# Digital_Clock.net
KiCad netlist of a schematic drawn in Altium Designer
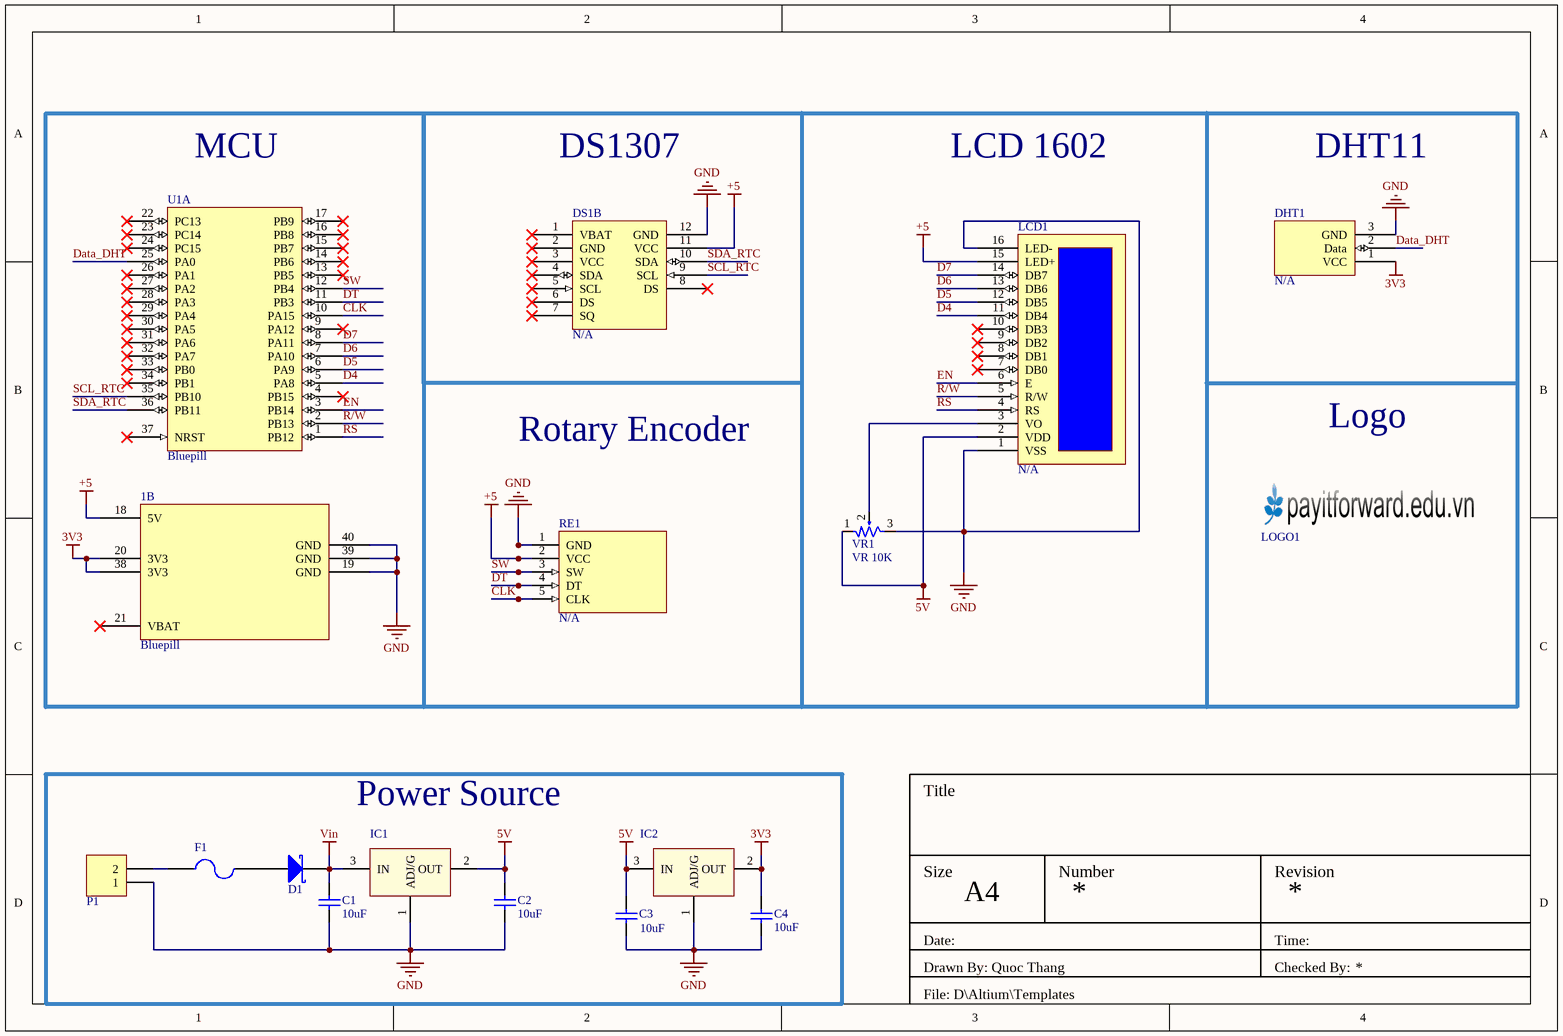
[diagram p0: Digital_Clock.SchDoc]

(export (version "E")
  (design (tool "Eeschema 10.0.6"))
  (components
    (comp (ref "1")
      (value "Bluepill")
      (footprint "STM32F103C8T6")
      (fields (field (name "MANUFACTURER") "STMicroelectronics"))
      (libsource (lib "Altium_library_module_kit") (part "STM32F103C8T6"))
    )
    (comp (ref "C1")
      (value "10uF")
      (footprint "CAP-SM-0805")
      (description "Capacitor")
      (fields (field (name "Comment") "Cap Non-Pol SMD"))
      (libsource (lib "PIF_Library") (part "Cap Non-Pol SMD"))
    )
    (comp (ref "C2")
      (value "10uF")
      (footprint "CAP-SM-0805")
      (description "Capacitor")
      (fields (field (name "Comment") "Cap Non-Pol SMD"))
      (libsource (lib "PIF_Library") (part "Cap Non-Pol SMD"))
    )
    (comp (ref "C3")
      (value "10uF")
      (footprint "CAP-SM-0805")
      (description "Capacitor")
      (fields (field (name "Comment") "Cap Non-Pol SMD"))
      (libsource (lib "PIF_Library") (part "Cap Non-Pol SMD"))
    )
    (comp (ref "C4")
      (value "10uF")
      (footprint "CAP-SM-0805")
      (description "Capacitor")
      (fields (field (name "Comment") "Cap Non-Pol SMD"))
      (libsource (lib "PIF_Library") (part "Cap Non-Pol SMD"))
    )
    (comp (ref "D1")
      (value "D Schottky")
      (footprint "SS34")
      (description "Schottky Diode")
      (fields (field (name "PUBLISHER") "Altium Limited"))
      (libsource (lib "PIF_Library") (part "D Schottky"))
    )
    (comp (ref "DHT1")
      (value "N/A")
      (footprint "DHT11")
      (description "Temperature Humidity Sensor 16bi")
      (fields (field (name "MANUFACTURER") "UNIVERSAL-SOLDER Electronics Ltd"))
      (libsource (lib "Altium_library_module_kit") (part "DHT11"))
    )
    (comp (ref "DS1")
      (value "N/A")
      (footprint "DS1307")
      (description "IC RTC CLOCK/CALENDAR I2C 8DIP")
      (fields (field (name "MANUFACTURER") "Analog Devices Inc./Maxim Integrated"))
      (libsource (lib "Altium_library_module_kit") (part "DS1307"))
    )
    (comp (ref "F1") (value "Fuse") (footprint "FUSE SMD") (libsource (lib "PIF_Library") (part "Fuse")))
    (comp (ref "IC1")
      (value "LM1117")
      (footprint "SOT223-4N")
      (description "Available in 1.8V, 2.5V, 2.85V, 3.3V, 5V, and  Adjustable Versions")
      (libsource (lib "PIF_Library") (part "LM1117"))
    )
    (comp (ref "IC2")
      (value "LM1117")
      (footprint "SOT223-4N")
      (description "Available in 1.8V, 2.5V, 2.85V, 3.3V, 5V, and  Adjustable Versions")
      (libsource (lib "PIF_Library") (part "LM1117"))
    )
    (comp (ref "LCD1")
      (value "N/A")
      (footprint "LCD1602")
      (description "BLUE LCD 1602 2x16 Character Mat")
      (fields (field (name "MANUFACTURER") "UNIVERSAL-SOLDER Electronics Ltd"))
      (libsource (lib "Altium_library_module_kit") (part "LCD1602"))
    )
    (comp (ref "LOGO1")
      (value "LOGO PIF")
      (footprint "PIF LOGO SMALL TOP")
      (libsource (lib "PIF_Library") (part "LOGO PIF"))
    )
    (comp (ref "P1")
      (value "Domino 2")
      (footprint "DOMINO 2- 5mm")
      (description "Domino, 2-Pin")
      (fields (field (name "PUBLISHER") "Altium Limited"))
      (libsource (lib "PIF_Library") (part "Domino 2"))
    )
    (comp (ref "RE1")
      (value "N/A")
      (footprint "Rotary_Encoder")
      (description "ROTARY ENCODER MECHANICAL 16PPR")
      (fields (field (name "MANUFACTURER") "CUI Devices"))
      (libsource (lib "Altium_library_module_kit") (part "Rotary Encoder"))
    )
    (comp (ref "U1")
      (value "Bluepill")
      (footprint "STM32F103C8T6")
      (fields (field (name "MANUFACTURER") "STMicroelectronics"))
      (libsource (lib "") (part "STM32F103C8T6_1"))
    )
    (comp (ref "VR1")
      (value "VR 10K")
      (footprint "Varistor 1")
      (description "Var Resistor")
      (fields (field (name "Comment") "10K"))
      (libsource (lib "PIF_Library") (part "Var Resistor"))
    )
  )
  (nets
    (net (code "1") (name "+5") (class "Default")
      (node (ref "1") (pin "18") (pinfunction "5V_18") (pintype "power_in"))
      (node (ref "DS1") (pin "11") (pinfunction "VCC_11") (pintype "power_in"))
      (node (ref "LCD1") (pin "15") (pinfunction "LED+_15") (pintype "power_in"))
      (node (ref "RE1") (pin "2") (pinfunction "VCC_2") (pintype "power_in"))
    )
    (net (code "2") (name "/CLK") (class "Default")
      (node (ref "RE1") (pin "5") (pinfunction "CLK_5") (pintype "input"))
      (node (ref "U1") (pin "10") (pinfunction "PA15_10") (pintype "bidirectional"))
    )
    (net (code "3") (name "/D4") (class "Default")
      (node (ref "LCD1") (pin "11") (pinfunction "DB4_11") (pintype "bidirectional"))
      (node (ref "U1") (pin "5") (pinfunction "PA8_5") (pintype "bidirectional"))
    )
    (net (code "4") (name "/D5") (class "Default")
      (node (ref "LCD1") (pin "12") (pinfunction "DB5_12") (pintype "bidirectional"))
      (node (ref "U1") (pin "6") (pinfunction "PA9_6") (pintype "bidirectional"))
    )
    (net (code "5") (name "/D6") (class "Default")
      (node (ref "LCD1") (pin "13") (pinfunction "DB6_13") (pintype "bidirectional"))
      (node (ref "U1") (pin "7") (pinfunction "PA10_7") (pintype "bidirectional"))
    )
    (net (code "6") (name "/D7") (class "Default")
      (node (ref "LCD1") (pin "14") (pinfunction "DB7_14") (pintype "bidirectional"))
      (node (ref "U1") (pin "8") (pinfunction "PA11_8") (pintype "bidirectional"))
    )
    (net (code "7") (name "/DT") (class "Default")
      (node (ref "RE1") (pin "4") (pinfunction "DT_4") (pintype "input"))
      (node (ref "U1") (pin "11") (pinfunction "PB3_11") (pintype "bidirectional"))
    )
    (net (code "8") (name "/Data_DHT") (class "Default")
      (node (ref "DHT1") (pin "2") (pinfunction "Data_2") (pintype "bidirectional"))
      (node (ref "U1") (pin "25") (pinfunction "PA0_25") (pintype "bidirectional"))
    )
    (net (code "9") (name "/EN") (class "Default")
      (node (ref "LCD1") (pin "6") (pinfunction "E_6") (pintype "input"))
      (node (ref "U1") (pin "3") (pinfunction "PB14_3") (pintype "bidirectional"))
    )
    (net (code "10") (name "/RS") (class "Default")
      (node (ref "LCD1") (pin "4") (pinfunction "RS_4") (pintype "input"))
      (node (ref "U1") (pin "1") (pinfunction "PB12_1") (pintype "bidirectional"))
    )
    (net (code "11") (name "/R{slash}W") (class "Default")
      (node (ref "LCD1") (pin "5") (pinfunction "R/W_5") (pintype "input"))
      (node (ref "U1") (pin "2") (pinfunction "PB13_2") (pintype "bidirectional"))
    )
    (net (code "12") (name "/SCL_RTC") (class "Default")
      (node (ref "DS1") (pin "9") (pinfunction "SCL_9") (pintype "input"))
      (node (ref "U1") (pin "35") (pinfunction "PB10_35") (pintype "bidirectional"))
    )
    (net (code "13") (name "/SDA_RTC") (class "Default")
      (node (ref "DS1") (pin "10") (pinfunction "SDA_10") (pintype "bidirectional"))
      (node (ref "U1") (pin "36") (pinfunction "PB11_36") (pintype "bidirectional"))
    )
    (net (code "14") (name "/SW") (class "Default")
      (node (ref "RE1") (pin "3") (pinfunction "SW_3") (pintype "input"))
      (node (ref "U1") (pin "12") (pinfunction "PB4_12") (pintype "bidirectional"))
    )
    (net (code "15") (name "3V3") (class "Default")
      (node (ref "1") (pin "20") (pinfunction "3V3_20") (pintype "power_in"))
      (node (ref "1") (pin "38") (pinfunction "3V3_38") (pintype "power_in"))
      (node (ref "C4") (pin "2") (pinfunction "2_2") (pintype "passive"))
      (node (ref "DHT1") (pin "1") (pinfunction "VCC_1") (pintype "power_in"))
      (node (ref "IC2") (pin "2") (pinfunction "OUT_2") (pintype "passive"))
    )
    (net (code "16") (name "5V") (class "Default")
      (node (ref "C2") (pin "2") (pinfunction "2_2") (pintype "passive"))
      (node (ref "C3") (pin "2") (pinfunction "2_2") (pintype "passive"))
      (node (ref "IC1") (pin "2") (pinfunction "OUT_2") (pintype "passive"))
      (node (ref "IC2") (pin "3") (pinfunction "IN_3") (pintype "passive"))
      (node (ref "LCD1") (pin "2") (pinfunction "VDD_2") (pintype "power_in"))
      (node (ref "VR1") (pin "1") (pinfunction "1_1") (pintype "passive"))
    )
    (net (code "17") (name "GND") (class "Default")
      (node (ref "1") (pin "19") (pinfunction "GND_19") (pintype "power_in"))
      (node (ref "1") (pin "39") (pinfunction "GND_39") (pintype "power_in"))
      (node (ref "1") (pin "40") (pinfunction "GND_40") (pintype "power_in"))
      (node (ref "C1") (pin "1") (pinfunction "1_1") (pintype "passive"))
      (node (ref "C2") (pin "1") (pinfunction "1_1") (pintype "passive"))
      (node (ref "C3") (pin "1") (pinfunction "1_1") (pintype "passive"))
      (node (ref "C4") (pin "1") (pinfunction "1_1") (pintype "passive"))
      (node (ref "DHT1") (pin "3") (pinfunction "GND_3") (pintype "power_in"))
      (node (ref "DS1") (pin "12") (pinfunction "GND_12") (pintype "power_in"))
      (node (ref "IC1") (pin "1") (pinfunction "ADJ/G_1") (pintype "passive"))
      (node (ref "IC2") (pin "1") (pinfunction "ADJ/G_1") (pintype "passive"))
      (node (ref "LCD1") (pin "1") (pinfunction "VSS_1") (pintype "power_in"))
      (node (ref "LCD1") (pin "16") (pinfunction "LED-_16") (pintype "power_in"))
      (node (ref "P1") (pin "1") (pinfunction "1_1") (pintype "passive"))
      (node (ref "RE1") (pin "1") (pinfunction "GND_1") (pintype "power_in"))
      (node (ref "VR1") (pin "3") (pinfunction "3_3") (pintype "passive"))
    )
    (net (code "18") (name "Net-(D1-A)") (class "Default")
      (node (ref "D1") (pin "1") (pinfunction "A_1") (pintype "passive"))
      (node (ref "F1") (pin "2") (pinfunction "2_2") (pintype "passive"))
    )
    (net (code "19") (name "Net-(F1-Pad1)") (class "Default")
      (node (ref "F1") (pin "1") (pinfunction "1_1") (pintype "passive"))
      (node (ref "P1") (pin "2") (pinfunction "2_2") (pintype "passive"))
    )
    (net (code "20") (name "Net-(LCD1-VO)") (class "Default")
      (node (ref "LCD1") (pin "3") (pinfunction "VO_3") (pintype "open_collector"))
      (node (ref "VR1") (pin "2") (pinfunction "2_2") (pintype "passive"))
    )
    (net (code "21") (name "Vin") (class "Default")
      (node (ref "C1") (pin "2") (pinfunction "2_2") (pintype "passive"))
      (node (ref "D1") (pin "2") (pinfunction "K_2") (pintype "passive"))
      (node (ref "IC1") (pin "3") (pinfunction "IN_3") (pintype "passive"))
    )
    (net (code "22") (name "unconnected-(1B-VBAT-Pad21)") (class "Default")
      (node (ref "1") (pin "21") (pinfunction "VBAT_21") (pintype "power_in+no_connect"))
    )
    (net (code "23") (name "unconnected-(DS1B-DS-Pad6)") (class "Default")
      (node (ref "DS1") (pin "6") (pinfunction "DS_6") (pintype "open_collector+no_connect"))
    )
    (net (code "24") (name "unconnected-(DS1B-DS-Pad8)") (class "Default")
      (node (ref "DS1") (pin "8") (pinfunction "DS_8") (pintype "open_collector+no_connect"))
    )
    (net (code "25") (name "unconnected-(DS1B-GND-Pad2)") (class "Default")
      (node (ref "DS1") (pin "2") (pinfunction "GND_2") (pintype "power_in+no_connect"))
    )
    (net (code "26") (name "unconnected-(DS1B-SCL-Pad5)") (class "Default")
      (node (ref "DS1") (pin "5") (pinfunction "SCL_5") (pintype "input+no_connect"))
    )
    (net (code "27") (name "unconnected-(DS1B-SDA-Pad4)") (class "Default")
      (node (ref "DS1") (pin "4") (pinfunction "SDA_4") (pintype "bidirectional+no_connect"))
    )
    (net (code "28") (name "unconnected-(DS1B-SQ-Pad7)") (class "Default")
      (node (ref "DS1") (pin "7") (pinfunction "SQ_7") (pintype "open_collector+no_connect"))
    )
    (net (code "29") (name "unconnected-(DS1B-VBAT-Pad1)") (class "Default")
      (node (ref "DS1") (pin "1") (pinfunction "VBAT_1") (pintype "power_in+no_connect"))
    )
    (net (code "30") (name "unconnected-(DS1B-VCC-Pad3)") (class "Default")
      (node (ref "DS1") (pin "3") (pinfunction "VCC_3") (pintype "power_in+no_connect"))
    )
    (net (code "31") (name "unconnected-(LCD1-DB0-Pad7)") (class "Default")
      (node (ref "LCD1") (pin "7") (pinfunction "DB0_7") (pintype "bidirectional+no_connect"))
    )
    (net (code "32") (name "unconnected-(LCD1-DB1-Pad8)") (class "Default")
      (node (ref "LCD1") (pin "8") (pinfunction "DB1_8") (pintype "bidirectional+no_connect"))
    )
    (net (code "33") (name "unconnected-(LCD1-DB2-Pad9)") (class "Default")
      (node (ref "LCD1") (pin "9") (pinfunction "DB2_9") (pintype "bidirectional+no_connect"))
    )
    (net (code "34") (name "unconnected-(LCD1-DB3-Pad10)") (class "Default")
      (node (ref "LCD1") (pin "10") (pinfunction "DB3_10") (pintype "bidirectional+no_connect"))
    )
    (net (code "35") (name "unconnected-(U1A-NRST-Pad37)") (class "Default")
      (node (ref "U1") (pin "37") (pinfunction "NRST_37") (pintype "input+no_connect"))
    )
    (net (code "36") (name "unconnected-(U1A-PA1-Pad26)") (class "Default")
      (node (ref "U1") (pin "26") (pinfunction "PA1_26") (pintype "bidirectional+no_connect"))
    )
    (net (code "37") (name "unconnected-(U1A-PA2-Pad27)") (class "Default")
      (node (ref "U1") (pin "27") (pinfunction "PA2_27") (pintype "bidirectional+no_connect"))
    )
    (net (code "38") (name "unconnected-(U1A-PA3-Pad28)") (class "Default")
      (node (ref "U1") (pin "28") (pinfunction "PA3_28") (pintype "bidirectional+no_connect"))
    )
    (net (code "39") (name "unconnected-(U1A-PA4-Pad29)") (class "Default")
      (node (ref "U1") (pin "29") (pinfunction "PA4_29") (pintype "bidirectional+no_connect"))
    )
    (net (code "40") (name "unconnected-(U1A-PA5-Pad30)") (class "Default")
      (node (ref "U1") (pin "30") (pinfunction "PA5_30") (pintype "bidirectional+no_connect"))
    )
    (net (code "41") (name "unconnected-(U1A-PA6-Pad31)") (class "Default")
      (node (ref "U1") (pin "31") (pinfunction "PA6_31") (pintype "bidirectional+no_connect"))
    )
    (net (code "42") (name "unconnected-(U1A-PA7-Pad32)") (class "Default")
      (node (ref "U1") (pin "32") (pinfunction "PA7_32") (pintype "bidirectional+no_connect"))
    )
    (net (code "43") (name "unconnected-(U1A-PA12-Pad9)") (class "Default")
      (node (ref "U1") (pin "9") (pinfunction "PA12_9") (pintype "bidirectional+no_connect"))
    )
    (net (code "44") (name "unconnected-(U1A-PB0-Pad33)") (class "Default")
      (node (ref "U1") (pin "33") (pinfunction "PB0_33") (pintype "bidirectional+no_connect"))
    )
    (net (code "45") (name "unconnected-(U1A-PB1-Pad34)") (class "Default")
      (node (ref "U1") (pin "34") (pinfunction "PB1_34") (pintype "bidirectional+no_connect"))
    )
    (net (code "46") (name "unconnected-(U1A-PB5-Pad13)") (class "Default")
      (node (ref "U1") (pin "13") (pinfunction "PB5_13") (pintype "bidirectional+no_connect"))
    )
    (net (code "47") (name "unconnected-(U1A-PB6-Pad14)") (class "Default")
      (node (ref "U1") (pin "14") (pinfunction "PB6_14") (pintype "bidirectional+no_connect"))
    )
    (net (code "48") (name "unconnected-(U1A-PB7-Pad15)") (class "Default")
      (node (ref "U1") (pin "15") (pinfunction "PB7_15") (pintype "bidirectional+no_connect"))
    )
    (net (code "49") (name "unconnected-(U1A-PB8-Pad16)") (class "Default")
      (node (ref "U1") (pin "16") (pinfunction "PB8_16") (pintype "bidirectional+no_connect"))
    )
    (net (code "50") (name "unconnected-(U1A-PB9-Pad17)") (class "Default")
      (node (ref "U1") (pin "17") (pinfunction "PB9_17") (pintype "bidirectional+no_connect"))
    )
    (net (code "51") (name "unconnected-(U1A-PB15-Pad4)") (class "Default")
      (node (ref "U1") (pin "4") (pinfunction "PB15_4") (pintype "bidirectional+no_connect"))
    )
    (net (code "52") (name "unconnected-(U1A-PC13-Pad22)") (class "Default")
      (node (ref "U1") (pin "22") (pinfunction "PC13_22") (pintype "bidirectional+no_connect"))
    )
    (net (code "53") (name "unconnected-(U1A-PC14-Pad23)") (class "Default")
      (node (ref "U1") (pin "23") (pinfunction "PC14_23") (pintype "bidirectional+no_connect"))
    )
    (net (code "54") (name "unconnected-(U1A-PC15-Pad24)") (class "Default")
      (node (ref "U1") (pin "24") (pinfunction "PC15_24") (pintype "bidirectional+no_connect"))
    )
  )
)
